# ind3200.net
KiCad netlist of a schematic drawn in Altium Designer
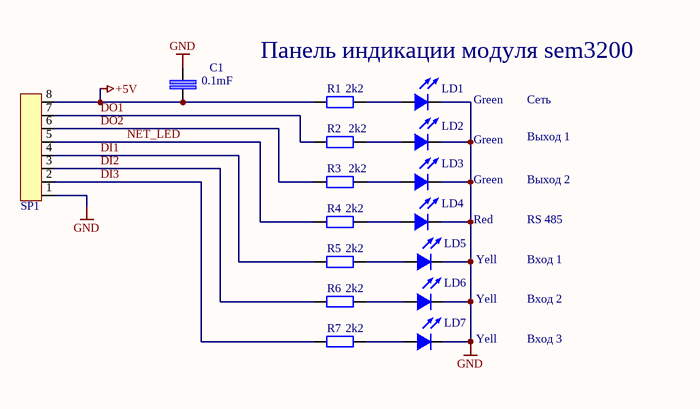
[diagram p0: ind3200.SchDoc]

(export (version "E")
  (design (tool "Eeschema 10.0.6"))
  (components
    (comp (ref "C1")
      (value "0.1mF")
      (footprint "CAPC2113X13N_0805")
      (fields (field (name "Comment") "0.1"))
      (libsource (lib "Lib_my1") (part "cap_1"))
    )
    (comp (ref "LD1") (value "Green") (footprint "LED_3") (libsource (lib "Lib_my1") (part "LED_1")))
    (comp (ref "LD2") (value "Green") (footprint "LED_3") (libsource (lib "Lib_my1") (part "LED_1")))
    (comp (ref "LD3") (value "Green") (footprint "LED_3") (libsource (lib "Lib_my1") (part "LED_1")))
    (comp (ref "LD4") (value "Red") (footprint "LED_3") (libsource (lib "Lib_my1") (part "LED_1")))
    (comp (ref "LD5") (value "Yell") (footprint "LED_3") (libsource (lib "Lib_my1") (part "LED_1")))
    (comp (ref "LD6") (value "Yell") (footprint "LED_3") (libsource (lib "Lib_my1") (part "LED_1")))
    (comp (ref "LD7") (value "Yell") (footprint "LED_3") (libsource (lib "Lib_my1") (part "LED_1")))
    (comp (ref "R1")
      (value "2k2")
      (footprint "RESC2113X0805N")
      (fields (field (name "Comment") "1k"))
      (libsource (lib "Lib_my1") (part "rez_1"))
    )
    (comp (ref "R2")
      (value "2k2")
      (footprint "RESC2113X0805N")
      (fields (field (name "Comment") "1k"))
      (libsource (lib "Lib_my1") (part "rez_1"))
    )
    (comp (ref "R3")
      (value "2k2")
      (footprint "RESC2113X0805N")
      (fields (field (name "Comment") "1k"))
      (libsource (lib "Lib_my1") (part "rez_1"))
    )
    (comp (ref "R4")
      (value "2k2")
      (footprint "RESC2113X0805N")
      (fields (field (name "Comment") "1k"))
      (libsource (lib "Lib_my1") (part "rez_1"))
    )
    (comp (ref "R5")
      (value "2k2")
      (footprint "RESC2113X0805N")
      (fields (field (name "Comment") "1k"))
      (libsource (lib "Lib_my1") (part "rez_1"))
    )
    (comp (ref "R6")
      (value "2k2")
      (footprint "RESC2113X0805N")
      (fields (field (name "Comment") "1k"))
      (libsource (lib "Lib_my1") (part "rez_1"))
    )
    (comp (ref "R7")
      (value "2k2")
      (footprint "RESC2113X0805N")
      (fields (field (name "Comment") "1k"))
      (libsource (lib "Lib_my1") (part "rez_1"))
    )
    (comp (ref "SP1") (value "SP1") (footprint "Conn8x1") (libsource (lib "Lib_my1") (part "Conn8x1")))
  )
  (nets
    (net (code "1") (name "+5V") (class "Default")
      (node (ref "C1") (pin "2") (pinfunction "2_2") (pintype "passive"))
      (node (ref "R1") (pin "2") (pinfunction "2_2") (pintype "passive"))
      (node (ref "SP1") (pin "8") (pinfunction "8_8") (pintype "passive"))
    )
    (net (code "2") (name "/DI1") (class "Default")
      (node (ref "R5") (pin "2") (pinfunction "2_2") (pintype "passive"))
      (node (ref "SP1") (pin "4") (pinfunction "4_4") (pintype "passive"))
    )
    (net (code "3") (name "/DI2") (class "Default")
      (node (ref "R6") (pin "2") (pinfunction "2_2") (pintype "passive"))
      (node (ref "SP1") (pin "3") (pinfunction "3_3") (pintype "passive"))
    )
    (net (code "4") (name "/DI3") (class "Default")
      (node (ref "R7") (pin "2") (pinfunction "2_2") (pintype "passive"))
      (node (ref "SP1") (pin "2") (pinfunction "2_2") (pintype "passive"))
    )
    (net (code "5") (name "/DO1") (class "Default")
      (node (ref "R2") (pin "2") (pinfunction "2_2") (pintype "passive"))
      (node (ref "SP1") (pin "7") (pinfunction "7_7") (pintype "passive"))
    )
    (net (code "6") (name "/DO2") (class "Default")
      (node (ref "R3") (pin "2") (pinfunction "2_2") (pintype "passive"))
      (node (ref "SP1") (pin "6") (pinfunction "6_6") (pintype "passive"))
    )
    (net (code "7") (name "/NET_LED") (class "Default")
      (node (ref "R4") (pin "2") (pinfunction "2_2") (pintype "passive"))
      (node (ref "SP1") (pin "5") (pinfunction "5_5") (pintype "passive"))
    )
    (net (code "8") (name "GND") (class "Default")
      (node (ref "C1") (pin "1") (pinfunction "1_1") (pintype "passive"))
      (node (ref "LD1") (pin "2") (pinfunction "2_2") (pintype "passive"))
      (node (ref "LD2") (pin "2") (pinfunction "2_2") (pintype "passive"))
      (node (ref "LD3") (pin "2") (pinfunction "2_2") (pintype "passive"))
      (node (ref "LD4") (pin "2") (pinfunction "2_2") (pintype "passive"))
      (node (ref "LD5") (pin "2") (pinfunction "2_2") (pintype "passive"))
      (node (ref "LD6") (pin "2") (pinfunction "2_2") (pintype "passive"))
      (node (ref "LD7") (pin "2") (pinfunction "2_2") (pintype "passive"))
      (node (ref "SP1") (pin "1") (pinfunction "1_1") (pintype "passive"))
    )
    (net (code "9") (name "Net-(LD1-Pad1)") (class "Default")
      (node (ref "LD1") (pin "1") (pinfunction "1_1") (pintype "passive"))
      (node (ref "R1") (pin "1") (pinfunction "1_1") (pintype "passive"))
    )
    (net (code "10") (name "Net-(LD2-Pad1)") (class "Default")
      (node (ref "LD2") (pin "1") (pinfunction "1_1") (pintype "passive"))
      (node (ref "R2") (pin "1") (pinfunction "1_1") (pintype "passive"))
    )
    (net (code "11") (name "Net-(LD3-Pad1)") (class "Default")
      (node (ref "LD3") (pin "1") (pinfunction "1_1") (pintype "passive"))
      (node (ref "R3") (pin "1") (pinfunction "1_1") (pintype "passive"))
    )
    (net (code "12") (name "Net-(LD4-Pad1)") (class "Default")
      (node (ref "LD4") (pin "1") (pinfunction "1_1") (pintype "passive"))
      (node (ref "R4") (pin "1") (pinfunction "1_1") (pintype "passive"))
    )
    (net (code "13") (name "Net-(LD5-Pad1)") (class "Default")
      (node (ref "LD5") (pin "1") (pinfunction "1_1") (pintype "passive"))
      (node (ref "R5") (pin "1") (pinfunction "1_1") (pintype "passive"))
    )
    (net (code "14") (name "Net-(LD6-Pad1)") (class "Default")
      (node (ref "LD6") (pin "1") (pinfunction "1_1") (pintype "passive"))
      (node (ref "R6") (pin "1") (pinfunction "1_1") (pintype "passive"))
    )
    (net (code "15") (name "Net-(LD7-Pad1)") (class "Default")
      (node (ref "LD7") (pin "1") (pinfunction "1_1") (pintype "passive"))
      (node (ref "R7") (pin "1") (pinfunction "1_1") (pintype "passive"))
    )
  )
)
